# Battery.net
KiCad netlist of a schematic drawn in Altium Designer
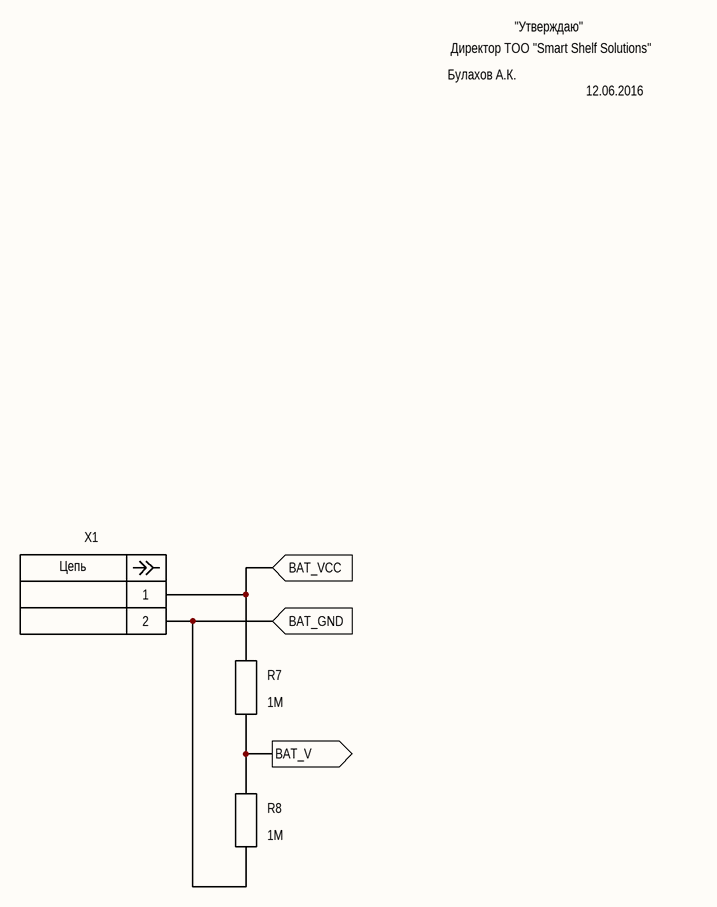
[diagram p0: Battery.SchDoc]

(export (version "E")
  (design (tool "Eeschema 10.0.6"))
  (components
    (comp (ref "R7")
      (value "1M")
      (footprint "RESC1608L")
      (description "Resistor Ceramic 1M 1608")
      (fields (field (name "MANUFACTURER") "Yageo") (field (name "TOLERANCE") "±5%"))
      (libsource (lib "Resistors") (part "RC0603JR-071ML"))
    )
    (comp (ref "R8")
      (value "1M")
      (footprint "RESC1608L")
      (description "Resistor Ceramic 1M 1608")
      (fields (field (name "MANUFACTURER") "Yageo") (field (name "TOLERANCE") "±5%"))
      (libsource (lib "Resistors") (part "RC0603JR-071ML"))
    )
    (comp (ref "X1")
      (value "B2B-XH-A")
      (footprint "B2B-XH-A")
      (description "Header, 2.54, 2p, Top")
      (fields (field (name "MANUFACTURER") "JST Sales America Inc"))
      (libsource (lib "Connectors") (part "B2B-XH-A"))
    )
  )
  (nets
    (net (code "1") (name "/BAT_GND") (class "Default")
      (node (ref "R8") (pin "2") (pinfunction "2_2") (pintype "passive"))
      (node (ref "X1") (pin "2") (pinfunction "2_2") (pintype "passive"))
    )
    (net (code "2") (name "/BAT_V") (class "Default")
      (node (ref "R7") (pin "2") (pinfunction "2_2") (pintype "passive"))
      (node (ref "R8") (pin "1") (pinfunction "1_1") (pintype "passive"))
    )
    (net (code "3") (name "/BAT_VCC") (class "Default")
      (node (ref "R7") (pin "1") (pinfunction "1_1") (pintype "passive"))
      (node (ref "X1") (pin "1") (pinfunction "1_1") (pintype "passive"))
    )
  )
)
